# SCH_Airliner_radio.net
KiCad netlist of a schematic drawn in EasyEDA
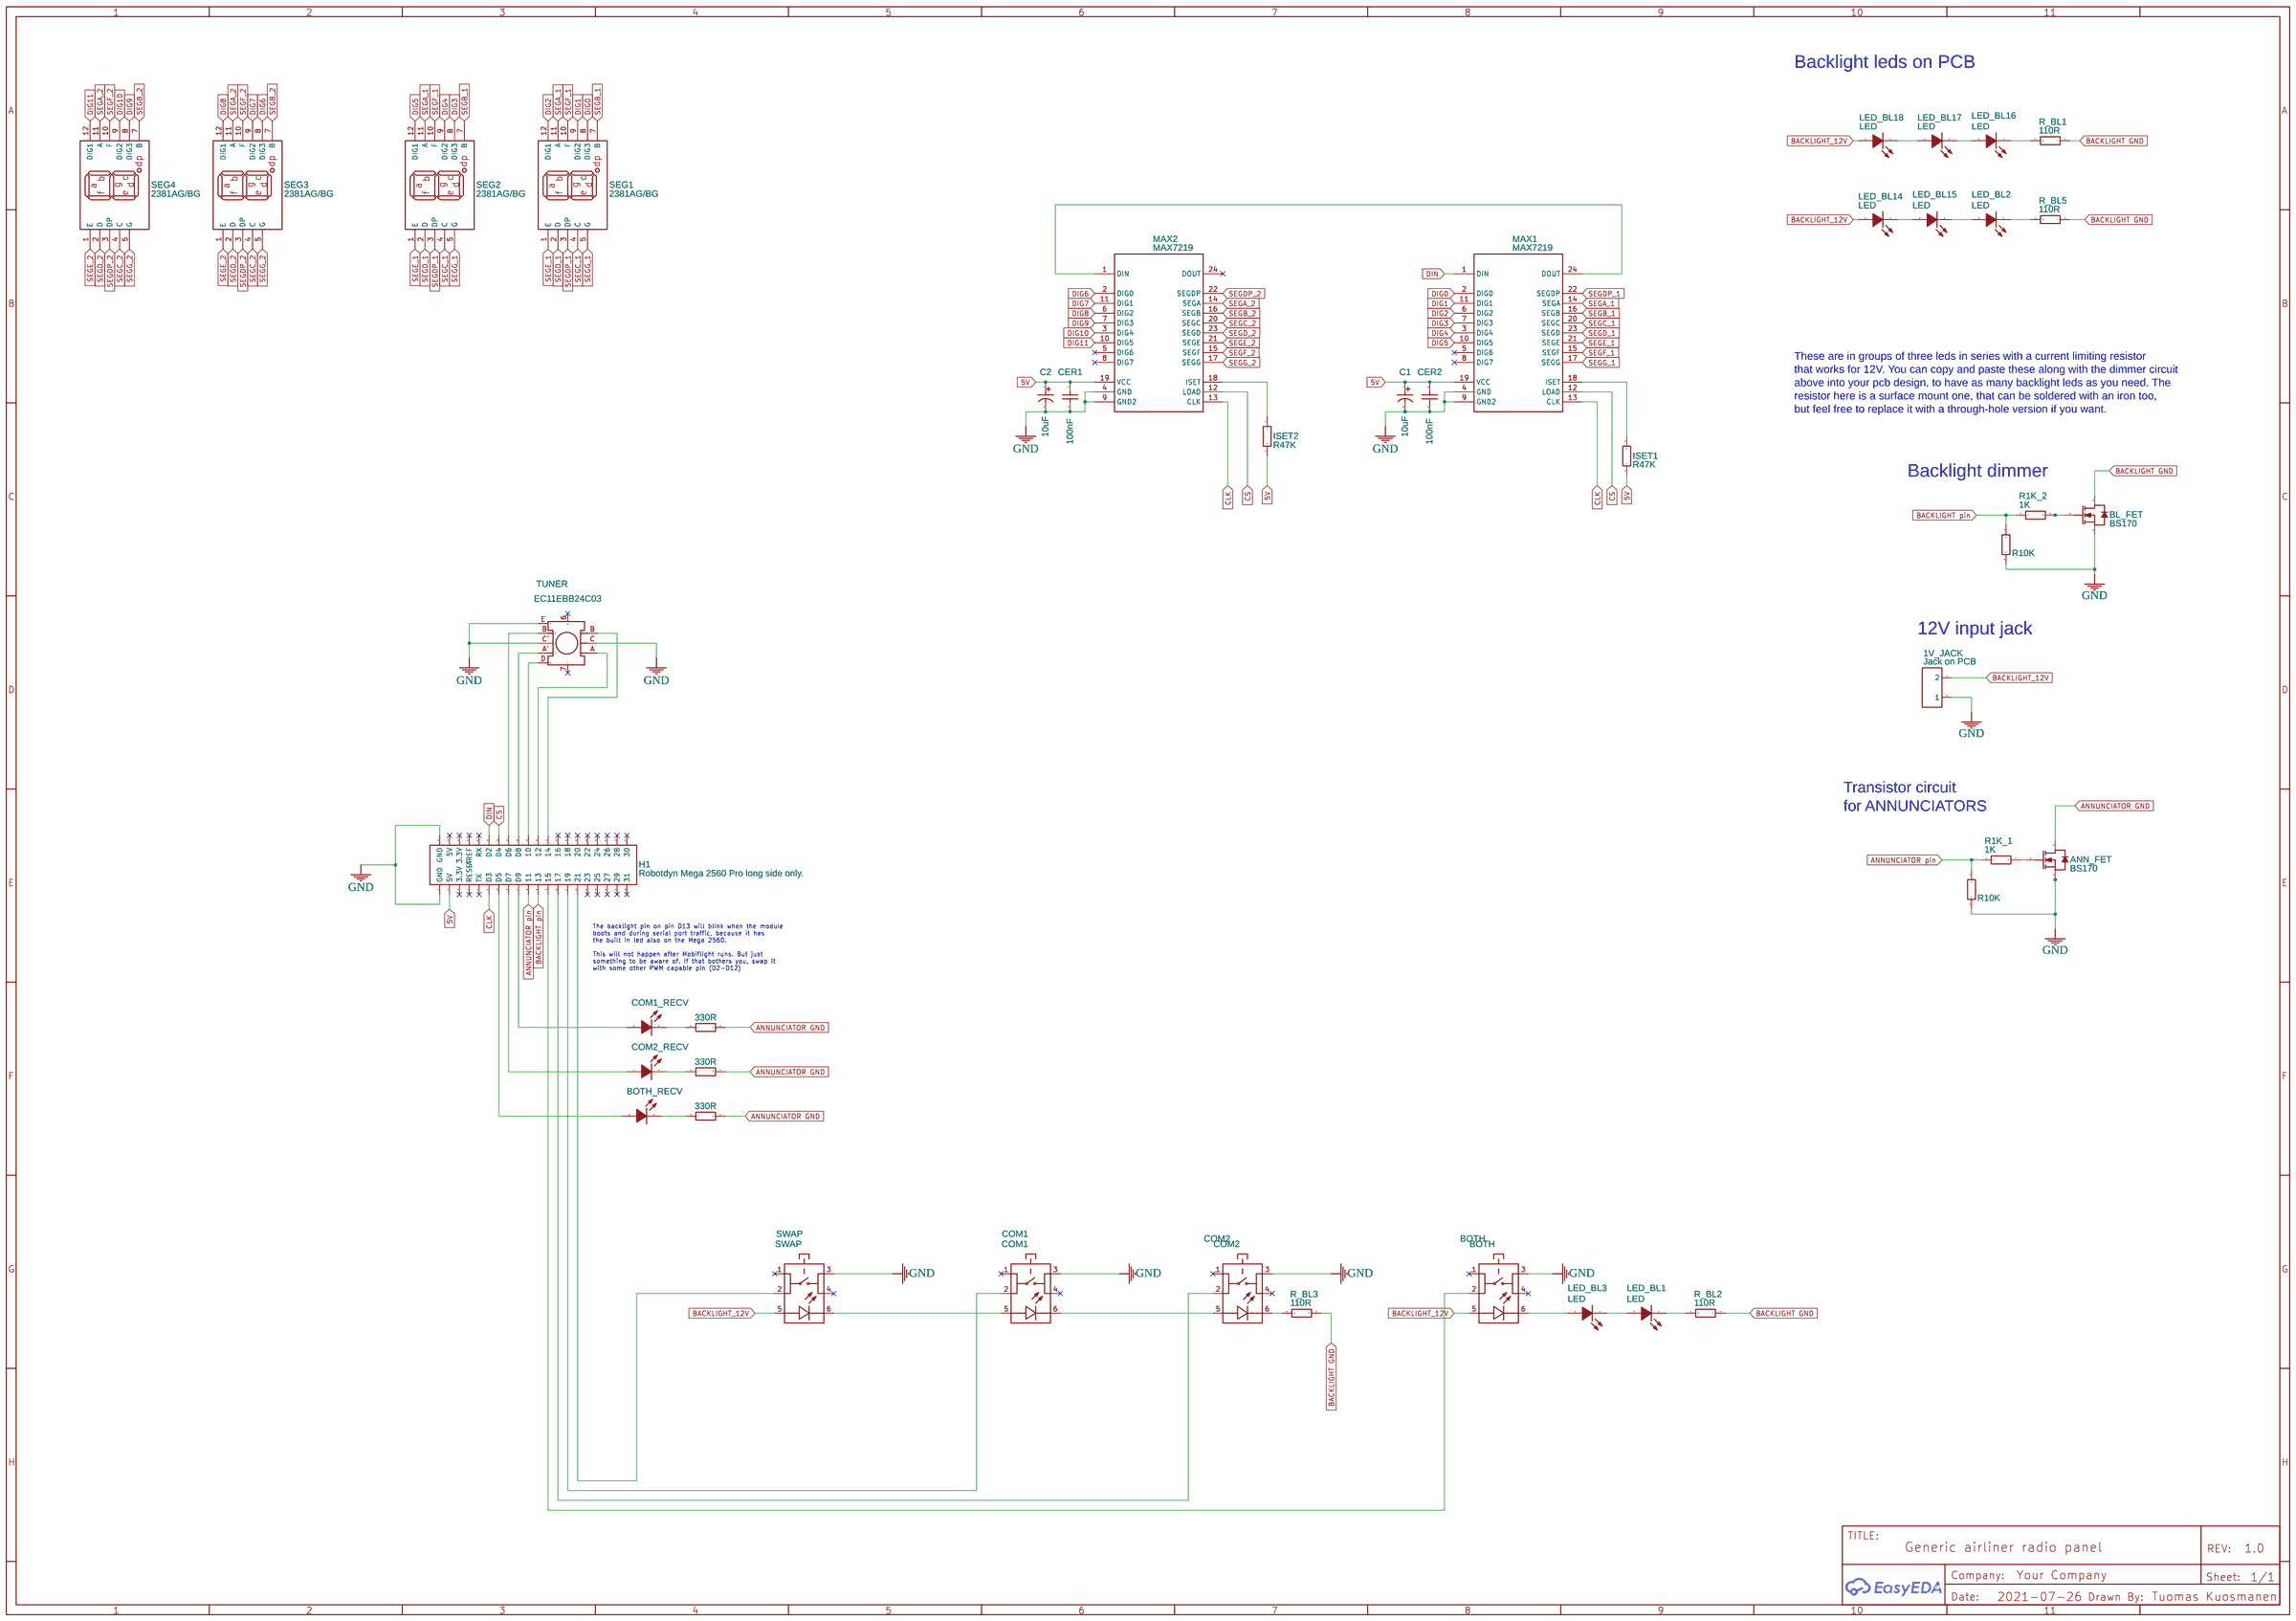
[diagram p0: schematic sheet]

(export (version "E")
  (design (tool "Eeschema 10.0.6"))
  (components
    (comp (ref "1MM_LED_THROUGH_HOLE")
      (value "COM2_RECV")
      (fields
        (field (name "BOM_Manufacturer Part") "LEDOrange orange 3AO4UD")
        (field (name "BOM_Supplier Part") "C62095")
      )
      (libsource (lib "") (part "LEDOrange orange 3AO4UD_2"))
    )
    (comp (ref "1V_JACK") (value "Jack on PCB") (libsource (lib "") (part "J-Header-Male-2.54_1x2")))
    (comp (ref "1_SURFACE_MOUNT_RESISTOR")
      (value "330R")
      (fields
        (field (name "BOM_Manufacturer Part") "1206W4F330LT5E")
        (field (name "BOM_Supplier Part") "C25337")
      )
      (libsource (lib "") (part "1206W4F330LT5E_1"))
    )
    (comp (ref "2MM_LED_THROUGH_HOLE")
      (value "BOTH_RECV")
      (fields
        (field (name "BOM_Manufacturer Part") "LEDOrange orange 3AO4UD")
        (field (name "BOM_Supplier Part") "C62095")
      )
      (libsource (lib "") (part "LEDOrange orange 3AO4UD_1"))
    )
    (comp (ref "2_SURFACE_MOUNT_RESISTOR")
      (value "330R")
      (fields
        (field (name "BOM_Manufacturer Part") "1206W4F330LT5E")
        (field (name "BOM_Supplier Part") "C25337")
      )
      (libsource (lib "") (part "1206W4F330LT5E"))
    )
    (comp (ref "3_SURFACE_MOUNT_RESISTOR")
      (value "330R")
      (fields
        (field (name "BOM_Manufacturer Part") "1206W4F330LT5E")
        (field (name "BOM_Supplier Part") "C25337")
      )
      (libsource (lib "") (part "1206W4F330LT5E_2"))
    )
    (comp (ref "5MM_LED_THROUGH_HOLE")
      (value "COM1_RECV")
      (fields
        (field (name "BOM_Manufacturer Part") "LEDOrange orange 3AO4UD")
        (field (name "BOM_Supplier Part") "C62095")
      )
      (libsource (lib "") (part "LEDOrange orange 3AO4UD"))
    )
    (comp (ref "ANN_FET")
      (value "BS170")
      (fields (field (name "BOM_Supplier Part") "C111691"))
      (libsource (lib "") (part "BS170"))
    )
    (comp (ref "BL_FET")
      (value "BS170")
      (fields (field (name "BOM_Supplier Part") "C111691"))
      (libsource (lib "") (part "BS170_1"))
    )
    (comp (ref "BOTH")
      (value "BOTH")
      (fields (field (name "BOM_Manufacturer Part") "1052612"))
      (libsource (lib "") (part "MULTIMEC 3FTH980 - Key Switch, 50 mA, 24 VDC, MEC_1"))
    )
    (comp (ref "C1")
      (value "10uF")
      (fields (field (name "BOM_Manufacturer Part") "10uf/100V") (field (name "BOM_Supplier Part") "C2029"))
      (libsource (lib "") (part "10uf/100V"))
    )
    (comp (ref "C2")
      (value "10uF")
      (fields (field (name "BOM_Manufacturer Part") "10uf/100V") (field (name "BOM_Supplier Part") "C2029"))
      (libsource (lib "") (part "10uf/100V"))
    )
    (comp (ref "CER1")
      (value "100nF")
      (fields
        (field (name "BOM_Manufacturer Part") "CS1F5.6Y5V1A104Z")
        (field (name "BOM_Supplier Part") "C9306")
      )
      (libsource (lib "") (part "CS1F5.6Y5V1A104Z"))
    )
    (comp (ref "CER2")
      (value "100nF")
      (fields
        (field (name "BOM_Manufacturer Part") "CS1F5.6Y5V1A104Z")
        (field (name "BOM_Supplier Part") "C9306")
      )
      (libsource (lib "") (part "CS1F5.6Y5V1A104Z"))
    )
    (comp (ref "COM1")
      (value "COM1")
      (fields (field (name "BOM_Manufacturer Part") "1052612"))
      (libsource (lib "") (part "MULTIMEC 3FTH980 - Key Switch, 50 mA, 24 VDC, MEC_2"))
    )
    (comp (ref "COM2")
      (value "COM2")
      (fields (field (name "BOM_Manufacturer Part") "1052612"))
      (libsource (lib "") (part "MULTIMEC 3FTH980 - Key Switch, 50 mA, 24 VDC, MEC_2"))
    )
    (comp (ref "H1")
      (value "Robotdyn Mega 2560 Pro long side only.")
      (fields
        (field (name "BOM_Manufacturer Part") "Header-Male-2.54_2x20")
        (field (name "BOM_Supplier Part") "C50980")
      )
      (libsource (lib "") (part "Header-Male-2.54_2x20"))
    )
    (comp (ref "ISET1")
      (value "R47K")
      (fields
        (field (name "BOM_Manufacturer Part") "1206W4J0331T5E")
        (field (name "BOM_Supplier Part") "C25374")
      )
      (libsource (lib "") (part "1206W4J0331T5E_3"))
    )
    (comp (ref "ISET2")
      (value "R47K")
      (fields
        (field (name "BOM_Manufacturer Part") "1206W4J0331T5E")
        (field (name "BOM_Supplier Part") "C25374")
      )
      (libsource (lib "") (part "1206W4J0331T5E_3"))
    )
    (comp (ref "LED_BL1")
      (value "LED")
      (fields
        (field (name "BOM_Manufacturer Part") "HQ17-2102UYOC")
        (field (name "BOM_Supplier Part") "C154481")
      )
      (libsource (lib "") (part "HQ17-2102UYOC"))
    )
    (comp (ref "LED_BL2")
      (value "LED")
      (fields
        (field (name "BOM_Manufacturer Part") "HQ17-2102UYOC")
        (field (name "BOM_Supplier Part") "C154481")
      )
      (libsource (lib "") (part "HQ17-2102UYOC"))
    )
    (comp (ref "LED_BL3")
      (value "LED")
      (fields
        (field (name "BOM_Manufacturer Part") "HQ17-2102UYOC")
        (field (name "BOM_Supplier Part") "C154481")
      )
      (libsource (lib "") (part "HQ17-2102UYOC"))
    )
    (comp (ref "LED_BL14")
      (value "LED")
      (fields
        (field (name "BOM_Manufacturer Part") "HQ17-2102UYOC")
        (field (name "BOM_Supplier Part") "C154481")
      )
      (libsource (lib "") (part "HQ17-2102UYOC"))
    )
    (comp (ref "LED_BL15")
      (value "LED")
      (fields
        (field (name "BOM_Manufacturer Part") "HQ17-2102UYOC")
        (field (name "BOM_Supplier Part") "C154481")
      )
      (libsource (lib "") (part "HQ17-2102UYOC"))
    )
    (comp (ref "LED_BL16")
      (value "LED")
      (fields
        (field (name "BOM_Manufacturer Part") "HQ17-2102UYOC")
        (field (name "BOM_Supplier Part") "C154481")
      )
      (libsource (lib "") (part "HQ17-2102UYOC"))
    )
    (comp (ref "LED_BL17")
      (value "LED")
      (fields
        (field (name "BOM_Manufacturer Part") "HQ17-2102UYOC")
        (field (name "BOM_Supplier Part") "C154481")
      )
      (libsource (lib "") (part "HQ17-2102UYOC"))
    )
    (comp (ref "LED_BL18")
      (value "LED")
      (fields
        (field (name "BOM_Manufacturer Part") "HQ17-2102UYOC")
        (field (name "BOM_Supplier Part") "C154481")
      )
      (libsource (lib "") (part "HQ17-2102UYOC"))
    )
    (comp (ref "MAX1") (value "MAX7219") (libsource (lib "") (part "MAX7219")))
    (comp (ref "MAX2") (value "MAX7219") (libsource (lib "") (part "MAX7219")))
    (comp (ref "R1K_1")
      (value "1K")
      (fields
        (field (name "BOM_Manufacturer Part") "1206W4J0331T5E")
        (field (name "BOM_Supplier Part") "C25374")
      )
      (libsource (lib "") (part "1206W4J0331T5E_2"))
    )
    (comp (ref "R1K_2")
      (value "1K")
      (fields
        (field (name "BOM_Manufacturer Part") "1206W4J0331T5E")
        (field (name "BOM_Supplier Part") "C25374")
      )
      (libsource (lib "") (part "1206W4J0331T5E_2"))
    )
    (comp (ref "R_ANN1")
      (value "R10K")
      (fields
        (field (name "BOM_Manufacturer Part") "1206W4J0331T5E")
        (field (name "BOM_Supplier Part") "C25374")
      )
      (libsource (lib "") (part "1206W4J0331T5E_1"))
    )
    (comp (ref "R_ANN5")
      (value "R10K")
      (fields
        (field (name "BOM_Manufacturer Part") "1206W4J0331T5E")
        (field (name "BOM_Supplier Part") "C25374")
      )
      (libsource (lib "") (part "1206W4J0331T5E_1"))
    )
    (comp (ref "R_BL1")
      (value "110R")
      (fields
        (field (name "BOM_Manufacturer Part") "1206W4J0331T5E")
        (field (name "BOM_Supplier Part") "C25374")
      )
      (libsource (lib "") (part "1206W4J0331T5E"))
    )
    (comp (ref "R_BL2")
      (value "110R")
      (fields
        (field (name "BOM_Manufacturer Part") "1206W4J0331T5E")
        (field (name "BOM_Supplier Part") "C25374")
      )
      (libsource (lib "") (part "1206W4J0331T5E"))
    )
    (comp (ref "R_BL3")
      (value "110R")
      (fields
        (field (name "BOM_Manufacturer Part") "1206W4J0331T5E")
        (field (name "BOM_Supplier Part") "C25374")
      )
      (libsource (lib "") (part "1206W4J0331T5E"))
    )
    (comp (ref "R_BL5")
      (value "110R")
      (fields
        (field (name "BOM_Manufacturer Part") "1206W4J0331T5E")
        (field (name "BOM_Supplier Part") "C25374")
      )
      (libsource (lib "") (part "1206W4J0331T5E"))
    )
    (comp (ref "SEG1") (value "2381AG/BG") (libsource (lib "") (part "2381AG/BG")))
    (comp (ref "SEG2") (value "2381AG/BG") (libsource (lib "") (part "2381AG/BG")))
    (comp (ref "SEG3") (value "2381AG/BG") (libsource (lib "") (part "2381AG/BG")))
    (comp (ref "SEG4") (value "2381AG/BG") (libsource (lib "") (part "2381AG/BG")))
    (comp (ref "SWAP")
      (value "SWAP")
      (fields (field (name "BOM_Manufacturer Part") "1052612"))
      (libsource (lib "") (part "MULTIMEC 3FTH980 - Key Switch, 50 mA, 24 VDC, MEC"))
    )
    (comp (ref "TUNER")
      (value "EC11EBB24C03")
      (fields (field (name "BOM_Supplier Part") "C470790"))
      (libsource (lib "") (part "EC11EBB24C03"))
    )
  )
  (nets
    (net (code "1") (name "5V") (class "Default")
      (node (ref "C1") (pin "1") (pinfunction "1_1") (pintype "input"))
      (node (ref "C2") (pin "1") (pinfunction "1_1") (pintype "input"))
      (node (ref "CER1") (pin "2") (pinfunction "2_2") (pintype "input"))
      (node (ref "CER2") (pin "2") (pinfunction "2_2") (pintype "input"))
      (node (ref "H1") (pin "3") (pinfunction "5V_3") (pintype "input"))
      (node (ref "ISET1") (pin "1") (pinfunction "1_1") (pintype "input"))
      (node (ref "ISET2") (pin "1") (pinfunction "1_1") (pintype "input"))
      (node (ref "MAX1") (pin "19") (pinfunction "VCC_19") (pintype "unspecified"))
      (node (ref "MAX2") (pin "19") (pinfunction "VCC_19") (pintype "unspecified"))
    )
    (net (code "2") (name "ANNUNCIATOR GND") (class "Default")
      (node (ref "1_SURFACE_MOUNT_RESISTOR") (pin "2") (pinfunction "2_2") (pintype "input"))
      (node (ref "2_SURFACE_MOUNT_RESISTOR") (pin "2") (pinfunction "2_2") (pintype "input"))
      (node (ref "3_SURFACE_MOUNT_RESISTOR") (pin "2") (pinfunction "2_2") (pintype "input"))
      (node (ref "ANN_FET") (pin "1") (pinfunction "D_1") (pintype "unspecified"))
    )
    (net (code "3") (name "ANNUNCIATOR pin") (class "Default")
      (node (ref "H1") (pin "19") (pinfunction "11_19") (pintype "input"))
      (node (ref "R1K_1") (pin "2") (pinfunction "2_2") (pintype "input"))
      (node (ref "R_ANN1") (pin "1") (pinfunction "1_1") (pintype "input"))
    )
    (net (code "4") (name "BACKLIGHT GND") (class "Default")
      (node (ref "BL_FET") (pin "1") (pinfunction "D_1") (pintype "unspecified"))
      (node (ref "R_BL1") (pin "1") (pinfunction "1_1") (pintype "input"))
      (node (ref "R_BL2") (pin "1") (pinfunction "1_1") (pintype "input"))
      (node (ref "R_BL3") (pin "1") (pinfunction "1_1") (pintype "input"))
      (node (ref "R_BL5") (pin "1") (pinfunction "1_1") (pintype "input"))
    )
    (net (code "5") (name "BACKLIGHT pin") (class "Default")
      (node (ref "H1") (pin "21") (pinfunction "13_21") (pintype "input"))
      (node (ref "R1K_2") (pin "2") (pinfunction "2_2") (pintype "input"))
      (node (ref "R_ANN5") (pin "1") (pinfunction "1_1") (pintype "input"))
    )
    (net (code "6") (name "BACKLIGHT_12V") (class "Default")
      (node (ref "1V_JACK") (pin "2") (pinfunction "2_2") (pintype "unspecified"))
      (node (ref "BOTH") (pin "5") (pinfunction "2_5") (pintype "unspecified"))
      (node (ref "LED_BL14") (pin "2") (pinfunction "A_2") (pintype "unspecified"))
      (node (ref "LED_BL18") (pin "2") (pinfunction "A_2") (pintype "unspecified"))
      (node (ref "SWAP") (pin "5") (pinfunction "2_5") (pintype "unspecified"))
    )
    (net (code "7") (name "CLK") (class "Default")
      (node (ref "H1") (pin "11") (pinfunction "D3_11") (pintype "input"))
      (node (ref "MAX1") (pin "13") (pinfunction "CLK_13") (pintype "unspecified"))
      (node (ref "MAX2") (pin "13") (pinfunction "CLK_13") (pintype "unspecified"))
    )
    (net (code "8") (name "CS") (class "Default")
      (node (ref "H1") (pin "14") (pinfunction "D4_14") (pintype "input"))
      (node (ref "MAX1") (pin "12") (pinfunction "LOAD_12") (pintype "unspecified"))
      (node (ref "MAX2") (pin "12") (pinfunction "LOAD_12") (pintype "unspecified"))
    )
    (net (code "9") (name "DIG0") (class "Default")
      (node (ref "MAX1") (pin "2") (pinfunction "DIG0_2") (pintype "unspecified"))
      (node (ref "SEG1") (pin "8") (pinfunction "DIG3_8") (pintype "input"))
    )
    (net (code "10") (name "DIG1") (class "Default")
      (node (ref "MAX1") (pin "11") (pinfunction "DIG1_11") (pintype "unspecified"))
      (node (ref "SEG1") (pin "9") (pinfunction "DIG2_9") (pintype "input"))
    )
    (net (code "11") (name "DIG2") (class "Default")
      (node (ref "MAX1") (pin "6") (pinfunction "DIG2_6") (pintype "unspecified"))
      (node (ref "SEG1") (pin "12") (pinfunction "DIG1_12") (pintype "input"))
    )
    (net (code "12") (name "DIG3") (class "Default")
      (node (ref "MAX1") (pin "7") (pinfunction "DIG3_7") (pintype "unspecified"))
      (node (ref "SEG2") (pin "8") (pinfunction "DIG3_8") (pintype "input"))
    )
    (net (code "13") (name "DIG4") (class "Default")
      (node (ref "MAX1") (pin "3") (pinfunction "DIG4_3") (pintype "unspecified"))
      (node (ref "SEG2") (pin "9") (pinfunction "DIG2_9") (pintype "input"))
    )
    (net (code "14") (name "DIG5") (class "Default")
      (node (ref "MAX1") (pin "10") (pinfunction "DIG5_10") (pintype "unspecified"))
      (node (ref "SEG2") (pin "12") (pinfunction "DIG1_12") (pintype "input"))
    )
    (net (code "15") (name "DIG6") (class "Default")
      (node (ref "MAX2") (pin "2") (pinfunction "DIG0_2") (pintype "unspecified"))
      (node (ref "SEG3") (pin "8") (pinfunction "DIG3_8") (pintype "input"))
    )
    (net (code "16") (name "DIG7") (class "Default")
      (node (ref "MAX2") (pin "11") (pinfunction "DIG1_11") (pintype "unspecified"))
      (node (ref "SEG3") (pin "9") (pinfunction "DIG2_9") (pintype "input"))
    )
    (net (code "17") (name "DIG8") (class "Default")
      (node (ref "MAX2") (pin "6") (pinfunction "DIG2_6") (pintype "unspecified"))
      (node (ref "SEG3") (pin "12") (pinfunction "DIG1_12") (pintype "input"))
    )
    (net (code "18") (name "DIG9") (class "Default")
      (node (ref "MAX2") (pin "7") (pinfunction "DIG3_7") (pintype "unspecified"))
      (node (ref "SEG4") (pin "8") (pinfunction "DIG3_8") (pintype "input"))
    )
    (net (code "19") (name "DIG10") (class "Default")
      (node (ref "MAX2") (pin "3") (pinfunction "DIG4_3") (pintype "unspecified"))
      (node (ref "SEG4") (pin "9") (pinfunction "DIG2_9") (pintype "input"))
    )
    (net (code "20") (name "DIG11") (class "Default")
      (node (ref "MAX2") (pin "10") (pinfunction "DIG5_10") (pintype "unspecified"))
      (node (ref "SEG4") (pin "12") (pinfunction "DIG1_12") (pintype "input"))
    )
    (net (code "21") (name "DIN") (class "Default")
      (node (ref "H1") (pin "12") (pinfunction "D2_12") (pintype "input"))
      (node (ref "MAX1") (pin "1") (pinfunction "DIN_1") (pintype "unspecified"))
    )
    (net (code "22") (name "GND") (class "Default")
      (node (ref "1V_JACK") (pin "1") (pinfunction "1_1") (pintype "unspecified"))
      (node (ref "ANN_FET") (pin "3") (pinfunction "S_3") (pintype "unspecified"))
      (node (ref "BL_FET") (pin "3") (pinfunction "S_3") (pintype "unspecified"))
      (node (ref "BOTH") (pin "3") (pinfunction "3_3") (pintype "unspecified"))
      (node (ref "C1") (pin "2") (pinfunction "2_2") (pintype "input"))
      (node (ref "C2") (pin "2") (pinfunction "2_2") (pintype "input"))
      (node (ref "CER1") (pin "1") (pinfunction "1_1") (pintype "input"))
      (node (ref "CER2") (pin "1") (pinfunction "1_1") (pintype "input"))
      (node (ref "COM1") (pin "3") (pinfunction "3_3") (pintype "unspecified"))
      (node (ref "COM2") (pin "3") (pinfunction "3_3") (pintype "unspecified"))
      (node (ref "H1") (pin "1") (pinfunction "GND_1") (pintype "input"))
      (node (ref "H1") (pin "2") (pinfunction "GND_2") (pintype "input"))
      (node (ref "MAX1") (pin "4") (pinfunction "GND_4") (pintype "unspecified"))
      (node (ref "MAX1") (pin "9") (pinfunction "GND2_9") (pintype "unspecified"))
      (node (ref "MAX2") (pin "4") (pinfunction "GND_4") (pintype "unspecified"))
      (node (ref "MAX2") (pin "9") (pinfunction "GND2_9") (pintype "unspecified"))
      (node (ref "R_ANN1") (pin "2") (pinfunction "2_2") (pintype "input"))
      (node (ref "R_ANN5") (pin "2") (pinfunction "2_2") (pintype "input"))
      (node (ref "SWAP") (pin "3") (pinfunction "3_3") (pintype "unspecified"))
      (node (ref "TUNER") (pin "C") (pinfunction "C_C") (pintype "unspecified"))
      (node (ref "TUNER") (pin "C'") (pinfunction "C'_C'") (pintype "unspecified"))
      (node (ref "TUNER") (pin "E") (pinfunction "E_E") (pintype "unspecified"))
    )
    (net (code "23") (name "Net-(1MM_LED_THROUGH_HOLE-A)") (class "Default")
      (node (ref "1MM_LED_THROUGH_HOLE") (pin "1") (pinfunction "A_1") (pintype "unspecified"))
      (node (ref "H1") (pin "15") (pinfunction "D7_15") (pintype "input"))
    )
    (net (code "24") (name "Net-(1MM_LED_THROUGH_HOLE-K)") (class "Default")
      (node (ref "1MM_LED_THROUGH_HOLE") (pin "2") (pinfunction "K_2") (pintype "unspecified"))
      (node (ref "1_SURFACE_MOUNT_RESISTOR") (pin "1") (pinfunction "1_1") (pintype "input"))
    )
    (net (code "25") (name "Net-(2MM_LED_THROUGH_HOLE-A)") (class "Default")
      (node (ref "2MM_LED_THROUGH_HOLE") (pin "1") (pinfunction "A_1") (pintype "unspecified"))
      (node (ref "H1") (pin "13") (pinfunction "D5_13") (pintype "input"))
    )
    (net (code "26") (name "Net-(2MM_LED_THROUGH_HOLE-K)") (class "Default")
      (node (ref "2MM_LED_THROUGH_HOLE") (pin "2") (pinfunction "K_2") (pintype "unspecified"))
      (node (ref "3_SURFACE_MOUNT_RESISTOR") (pin "1") (pinfunction "1_1") (pintype "input"))
    )
    (net (code "27") (name "Net-(5MM_LED_THROUGH_HOLE-A)") (class "Default")
      (node (ref "5MM_LED_THROUGH_HOLE") (pin "1") (pinfunction "A_1") (pintype "unspecified"))
      (node (ref "H1") (pin "17") (pinfunction "D9_17") (pintype "input"))
    )
    (net (code "28") (name "Net-(5MM_LED_THROUGH_HOLE-K)") (class "Default")
      (node (ref "2_SURFACE_MOUNT_RESISTOR") (pin "1") (pinfunction "1_1") (pintype "input"))
      (node (ref "5MM_LED_THROUGH_HOLE") (pin "2") (pinfunction "K_2") (pintype "unspecified"))
    )
    (net (code "29") (name "Net-(ANN_FET-G)") (class "Default")
      (node (ref "ANN_FET") (pin "2") (pinfunction "G_2") (pintype "unspecified"))
      (node (ref "R1K_1") (pin "1") (pinfunction "1_1") (pintype "input"))
    )
    (net (code "30") (name "Net-(BL_FET-G)") (class "Default")
      (node (ref "BL_FET") (pin "2") (pinfunction "G_2") (pintype "unspecified"))
      (node (ref "R1K_2") (pin "1") (pinfunction "1_1") (pintype "input"))
    )
    (net (code "31") (name "Net-(COM1-2-Pad5)") (class "Default")
      (node (ref "COM1") (pin "5") (pinfunction "2_5") (pintype "unspecified"))
      (node (ref "SWAP") (pin "6") (pinfunction "4_6") (pintype "unspecified"))
    )
    (net (code "32") (name "Net-(COM1-4-Pad6)") (class "Default")
      (node (ref "COM1") (pin "6") (pinfunction "4_6") (pintype "unspecified"))
      (node (ref "COM2") (pin "5") (pinfunction "2_5") (pintype "unspecified"))
    )
    (net (code "33") (name "Net-(COM2-4-Pad6)") (class "Default")
      (node (ref "COM2") (pin "6") (pinfunction "4_6") (pintype "unspecified"))
      (node (ref "R_BL3") (pin "2") (pinfunction "2_2") (pintype "input"))
    )
    (net (code "34") (name "Net-(H1-10)") (class "Default")
      (node (ref "H1") (pin "20") (pinfunction "10_20") (pintype "input"))
      (node (ref "TUNER") (pin "D") (pinfunction "D_D") (pintype "unspecified"))
    )
    (net (code "35") (name "Net-(H1-12)") (class "Default")
      (node (ref "H1") (pin "22") (pinfunction "12_22") (pintype "input"))
      (node (ref "TUNER") (pin "A") (pinfunction "A_A") (pintype "unspecified"))
    )
    (net (code "36") (name "Net-(H1-14)") (class "Default")
      (node (ref "H1") (pin "24") (pinfunction "14_24") (pintype "input"))
      (node (ref "TUNER") (pin "B") (pinfunction "B_B") (pintype "unspecified"))
    )
    (net (code "37") (name "Net-(H1-15)") (class "Default")
      (node (ref "BOTH") (pin "2") (pinfunction "2_2") (pintype "unspecified"))
      (node (ref "H1") (pin "23") (pinfunction "15_23") (pintype "input"))
    )
    (net (code "38") (name "Net-(H1-17)") (class "Default")
      (node (ref "COM2") (pin "2") (pinfunction "2_2") (pintype "unspecified"))
      (node (ref "H1") (pin "25") (pinfunction "17_25") (pintype "input"))
    )
    (net (code "39") (name "Net-(H1-19)") (class "Default")
      (node (ref "COM1") (pin "2") (pinfunction "2_2") (pintype "unspecified"))
      (node (ref "H1") (pin "27") (pinfunction "19_27") (pintype "input"))
    )
    (net (code "40") (name "Net-(H1-21)") (class "Default")
      (node (ref "H1") (pin "29") (pinfunction "21_29") (pintype "input"))
      (node (ref "SWAP") (pin "2") (pinfunction "2_2") (pintype "unspecified"))
    )
    (net (code "41") (name "Net-(H1-D6)") (class "Default")
      (node (ref "H1") (pin "16") (pinfunction "D6_16") (pintype "input"))
      (node (ref "TUNER") (pin "B'") (pinfunction "B'_B'") (pintype "unspecified"))
    )
    (net (code "42") (name "Net-(H1-D8)") (class "Default")
      (node (ref "H1") (pin "18") (pinfunction "D8_18") (pintype "input"))
      (node (ref "TUNER") (pin "A'") (pinfunction "A'_A'") (pintype "unspecified"))
    )
    (net (code "43") (name "Net-(LED_BL1-A)") (class "Default")
      (node (ref "LED_BL1") (pin "2") (pinfunction "A_2") (pintype "unspecified"))
      (node (ref "LED_BL3") (pin "1") (pinfunction "K_1") (pintype "unspecified"))
    )
    (net (code "44") (name "Net-(LED_BL1-K)") (class "Default")
      (node (ref "LED_BL1") (pin "1") (pinfunction "K_1") (pintype "unspecified"))
      (node (ref "R_BL2") (pin "2") (pinfunction "2_2") (pintype "input"))
    )
    (net (code "45") (name "Net-(LED_BL2-K)") (class "Default")
      (node (ref "LED_BL2") (pin "1") (pinfunction "K_1") (pintype "unspecified"))
      (node (ref "R_BL5") (pin "2") (pinfunction "2_2") (pintype "input"))
    )
    (net (code "46") (name "Net-(LED_BL3-A)") (class "Default")
      (node (ref "BOTH") (pin "6") (pinfunction "4_6") (pintype "unspecified"))
      (node (ref "LED_BL3") (pin "2") (pinfunction "A_2") (pintype "unspecified"))
    )
    (net (code "47") (name "Net-(LED_BL14-K)") (class "Default")
      (node (ref "LED_BL14") (pin "1") (pinfunction "K_1") (pintype "unspecified"))
      (node (ref "LED_BL15") (pin "2") (pinfunction "A_2") (pintype "unspecified"))
    )
    (net (code "48") (name "Net-(LED_BL15-K)") (class "Default")
      (node (ref "LED_BL15") (pin "1") (pinfunction "K_1") (pintype "unspecified"))
      (node (ref "LED_BL2") (pin "2") (pinfunction "A_2") (pintype "unspecified"))
    )
    (net (code "49") (name "Net-(LED_BL16-A)") (class "Default")
      (node (ref "LED_BL16") (pin "2") (pinfunction "A_2") (pintype "unspecified"))
      (node (ref "LED_BL17") (pin "1") (pinfunction "K_1") (pintype "unspecified"))
    )
    (net (code "50") (name "Net-(LED_BL16-K)") (class "Default")
      (node (ref "LED_BL16") (pin "1") (pinfunction "K_1") (pintype "unspecified"))
      (node (ref "R_BL1") (pin "2") (pinfunction "2_2") (pintype "input"))
    )
    (net (code "51") (name "Net-(LED_BL17-A)") (class "Default")
      (node (ref "LED_BL17") (pin "2") (pinfunction "A_2") (pintype "unspecified"))
      (node (ref "LED_BL18") (pin "1") (pinfunction "K_1") (pintype "unspecified"))
    )
    (net (code "52") (name "Net-(MAX1-DOUT)") (class "Default")
      (node (ref "MAX1") (pin "24") (pinfunction "DOUT_24") (pintype "unspecified"))
      (node (ref "MAX2") (pin "1") (pinfunction "DIN_1") (pintype "unspecified"))
    )
    (net (code "53") (name "Net-(MAX1-ISET)") (class "Default")
      (node (ref "ISET1") (pin "2") (pinfunction "2_2") (pintype "input"))
      (node (ref "MAX1") (pin "18") (pinfunction "ISET_18") (pintype "unspecified"))
    )
    (net (code "54") (name "Net-(MAX2-ISET)") (class "Default")
      (node (ref "ISET2") (pin "2") (pinfunction "2_2") (pintype "input"))
      (node (ref "MAX2") (pin "18") (pinfunction "ISET_18") (pintype "unspecified"))
    )
    (net (code "55") (name "SEGA_1") (class "Default")
      (node (ref "MAX1") (pin "14") (pinfunction "SEGA_14") (pintype "unspecified"))
      (node (ref "SEG1") (pin "11") (pinfunction "A_11") (pintype "input"))
      (node (ref "SEG2") (pin "11") (pinfunction "A_11") (pintype "input"))
    )
    (net (code "56") (name "SEGA_2") (class "Default")
      (node (ref "MAX2") (pin "14") (pinfunction "SEGA_14") (pintype "unspecified"))
      (node (ref "SEG3") (pin "11") (pinfunction "A_11") (pintype "input"))
      (node (ref "SEG4") (pin "11") (pinfunction "A_11") (pintype "input"))
    )
    (net (code "57") (name "SEGB_1") (class "Default")
      (node (ref "MAX1") (pin "16") (pinfunction "SEGB_16") (pintype "unspecified"))
      (node (ref "SEG1") (pin "7") (pinfunction "B_7") (pintype "input"))
      (node (ref "SEG2") (pin "7") (pinfunction "B_7") (pintype "input"))
    )
    (net (code "58") (name "SEGB_2") (class "Default")
      (node (ref "MAX2") (pin "16") (pinfunction "SEGB_16") (pintype "unspecified"))
      (node (ref "SEG3") (pin "7") (pinfunction "B_7") (pintype "input"))
      (node (ref "SEG4") (pin "7") (pinfunction "B_7") (pintype "input"))
    )
    (net (code "59") (name "SEGC_1") (class "Default")
      (node (ref "MAX1") (pin "20") (pinfunction "SEGC_20") (pintype "unspecified"))
      (node (ref "SEG1") (pin "4") (pinfunction "C_4") (pintype "input"))
      (node (ref "SEG2") (pin "4") (pinfunction "C_4") (pintype "input"))
    )
    (net (code "60") (name "SEGC_2") (class "Default")
      (node (ref "MAX2") (pin "20") (pinfunction "SEGC_20") (pintype "unspecified"))
      (node (ref "SEG3") (pin "4") (pinfunction "C_4") (pintype "input"))
      (node (ref "SEG4") (pin "4") (pinfunction "C_4") (pintype "input"))
    )
    (net (code "61") (name "SEGDP_1") (class "Default")
      (node (ref "MAX1") (pin "22") (pinfunction "SEGDP_22") (pintype "unspecified"))
      (node (ref "SEG1") (pin "3") (pinfunction "DP_3") (pintype "input"))
      (node (ref "SEG2") (pin "3") (pinfunction "DP_3") (pintype "input"))
    )
    (net (code "62") (name "SEGDP_2") (class "Default")
      (node (ref "MAX2") (pin "22") (pinfunction "SEGDP_22") (pintype "unspecified"))
      (node (ref "SEG3") (pin "3") (pinfunction "DP_3") (pintype "input"))
      (node (ref "SEG4") (pin "3") (pinfunction "DP_3") (pintype "input"))
    )
    (net (code "63") (name "SEGD_1") (class "Default")
      (node (ref "MAX1") (pin "23") (pinfunction "SEGD_23") (pintype "unspecified"))
      (node (ref "SEG1") (pin "2") (pinfunction "D_2") (pintype "input"))
      (node (ref "SEG2") (pin "2") (pinfunction "D_2") (pintype "input"))
    )
    (net (code "64") (name "SEGD_2") (class "Default")
      (node (ref "MAX2") (pin "23") (pinfunction "SEGD_23") (pintype "unspecified"))
      (node (ref "SEG3") (pin "2") (pinfunction "D_2") (pintype "input"))
      (node (ref "SEG4") (pin "2") (pinfunction "D_2") (pintype "input"))
    )
    (net (code "65") (name "SEGE_1") (class "Default")
      (node (ref "MAX1") (pin "21") (pinfunction "SEGE_21") (pintype "unspecified"))
      (node (ref "SEG1") (pin "1") (pinfunction "E_1") (pintype "input"))
      (node (ref "SEG2") (pin "1") (pinfunction "E_1") (pintype "input"))
    )
    (net (code "66") (name "SEGE_2") (class "Default")
      (node (ref "MAX2") (pin "21") (pinfunction "SEGE_21") (pintype "unspecified"))
      (node (ref "SEG3") (pin "1") (pinfunction "E_1") (pintype "input"))
      (node (ref "SEG4") (pin "1") (pinfunction "E_1") (pintype "input"))
    )
    (net (code "67") (name "SEGF_1") (class "Default")
      (node (ref "MAX1") (pin "15") (pinfunction "SEGF_15") (pintype "unspecified"))
      (node (ref "SEG1") (pin "10") (pinfunction "F_10") (pintype "input"))
      (node (ref "SEG2") (pin "10") (pinfunction "F_10") (pintype "input"))
    )
    (net (code "68") (name "SEGF_2") (class "Default")
      (node (ref "MAX2") (pin "15") (pinfunction "SEGF_15") (pintype "unspecified"))
      (node (ref "SEG3") (pin "10") (pinfunction "F_10") (pintype "input"))
      (node (ref "SEG4") (pin "10") (pinfunction "F_10") (pintype "input"))
    )
    (net (code "69") (name "SEGG_1") (class "Default")
      (node (ref "MAX1") (pin "17") (pinfunction "SEGG_17") (pintype "unspecified"))
      (node (ref "SEG1") (pin "5") (pinfunction "G_5") (pintype "input"))
      (node (ref "SEG2") (pin "5") (pinfunction "G_5") (pintype "input"))
    )
    (net (code "70") (name "SEGG_2") (class "Default")
      (node (ref "MAX2") (pin "17") (pinfunction "SEGG_17") (pintype "unspecified"))
      (node (ref "SEG3") (pin "5") (pinfunction "G_5") (pintype "input"))
      (node (ref "SEG4") (pin "5") (pinfunction "G_5") (pintype "input"))
    )
    (net (code "71") (name "unconnected-(BOTH-Pad1)") (class "Default")
      (node (ref "BOTH") (pin "1") (pinfunction "1_1") (pintype "unspecified+no_connect"))
    )
    (net (code "72") (name "unconnected-(BOTH-Pad4)") (class "Default")
      (node (ref "BOTH") (pin "4") (pinfunction "4_4") (pintype "unspecified+no_connect"))
    )
    (net (code "73") (name "unconnected-(COM1-Pad1)") (class "Default")
      (node (ref "COM1") (pin "1") (pinfunction "1_1") (pintype "unspecified+no_connect"))
    )
    (net (code "74") (name "unconnected-(COM1-Pad4)") (class "Default")
      (node (ref "COM1") (pin "4") (pinfunction "4_4") (pintype "unspecified+no_connect"))
    )
    (net (code "75") (name "unconnected-(COM2-Pad1)") (class "Default")
      (node (ref "COM2") (pin "1") (pinfunction "1_1") (pintype "unspecified+no_connect"))
    )
    (net (code "76") (name "unconnected-(COM2-Pad4)") (class "Default")
      (node (ref "COM2") (pin "4") (pinfunction "4_4") (pintype "unspecified+no_connect"))
    )
    (net (code "77") (name "unconnected-(H1-3.3V-Pad5)") (class "Default")
      (node (ref "H1") (pin "5") (pinfunction "3.3V_5") (pintype "input+no_connect"))
    )
    (net (code "78") (name "unconnected-(H1-3.3V-Pad6)") (class "Default")
      (node (ref "H1") (pin "6") (pinfunction "3.3V_6") (pintype "input+no_connect"))
    )
    (net (code "79") (name "unconnected-(H1-5V-Pad4)") (class "Default")
      (node (ref "H1") (pin "4") (pinfunction "5V_4") (pintype "input+no_connect"))
    )
    (net (code "80") (name "unconnected-(H1-16-Pad26)") (class "Default")
      (node (ref "H1") (pin "26") (pinfunction "16_26") (pintype "input+no_connect"))
    )
    (net (code "81") (name "unconnected-(H1-18-Pad28)") (class "Default")
      (node (ref "H1") (pin "28") (pinfunction "18_28") (pintype "input+no_connect"))
    )
    (net (code "82") (name "unconnected-(H1-20-Pad30)") (class "Default")
      (node (ref "H1") (pin "30") (pinfunction "20_30") (pintype "input+no_connect"))
    )
    (net (code "83") (name "unconnected-(H1-22-Pad32)") (class "Default")
      (node (ref "H1") (pin "32") (pinfunction "22_32") (pintype "input+no_connect"))
    )
    (net (code "84") (name "unconnected-(H1-23-Pad31)") (class "Default")
      (node (ref "H1") (pin "31") (pinfunction "23_31") (pintype "input+no_connect"))
    )
    (net (code "85") (name "unconnected-(H1-24-Pad34)") (class "Default")
      (node (ref "H1") (pin "34") (pinfunction "24_34") (pintype "input+no_connect"))
    )
    (net (code "86") (name "unconnected-(H1-25-Pad33)") (class "Default")
      (node (ref "H1") (pin "33") (pinfunction "25_33") (pintype "input+no_connect"))
    )
    (net (code "87") (name "unconnected-(H1-26-Pad36)") (class "Default")
      (node (ref "H1") (pin "36") (pinfunction "26_36") (pintype "input+no_connect"))
    )
    (net (code "88") (name "unconnected-(H1-27-Pad35)") (class "Default")
      (node (ref "H1") (pin "35") (pinfunction "27_35") (pintype "input+no_connect"))
    )
    (net (code "89") (name "unconnected-(H1-28-Pad38)") (class "Default")
      (node (ref "H1") (pin "38") (pinfunction "28_38") (pintype "input+no_connect"))
    )
    (net (code "90") (name "unconnected-(H1-29-Pad37)") (class "Default")
      (node (ref "H1") (pin "37") (pinfunction "29_37") (pintype "input+no_connect"))
    )
    (net (code "91") (name "unconnected-(H1-30-Pad40)") (class "Default")
      (node (ref "H1") (pin "40") (pinfunction "30_40") (pintype "input+no_connect"))
    )
    (net (code "92") (name "unconnected-(H1-31-Pad39)") (class "Default")
      (node (ref "H1") (pin "39") (pinfunction "31_39") (pintype "input+no_connect"))
    )
    (net (code "93") (name "unconnected-(H1-AREF-Pad8)") (class "Default")
      (node (ref "H1") (pin "8") (pinfunction "AREF_8") (pintype "input+no_connect"))
    )
    (net (code "94") (name "unconnected-(H1-RESET-Pad7)") (class "Default")
      (node (ref "H1") (pin "7") (pinfunction "RESET_7") (pintype "input+no_connect"))
    )
    (net (code "95") (name "unconnected-(H1-RX-Pad10)") (class "Default")
      (node (ref "H1") (pin "10") (pinfunction "RX_10") (pintype "input+no_connect"))
    )
    (net (code "96") (name "unconnected-(H1-TX-Pad9)") (class "Default")
      (node (ref "H1") (pin "9") (pinfunction "TX_9") (pintype "input+no_connect"))
    )
    (net (code "97") (name "unconnected-(MAX1-DIG6-Pad5)") (class "Default")
      (node (ref "MAX1") (pin "5") (pinfunction "DIG6_5") (pintype "unspecified+no_connect"))
    )
    (net (code "98") (name "unconnected-(MAX1-DIG7-Pad8)") (class "Default")
      (node (ref "MAX1") (pin "8") (pinfunction "DIG7_8") (pintype "unspecified+no_connect"))
    )
    (net (code "99") (name "unconnected-(MAX2-DIG6-Pad5)") (class "Default")
      (node (ref "MAX2") (pin "5") (pinfunction "DIG6_5") (pintype "unspecified+no_connect"))
    )
    (net (code "100") (name "unconnected-(MAX2-DIG7-Pad8)") (class "Default")
      (node (ref "MAX2") (pin "8") (pinfunction "DIG7_8") (pintype "unspecified+no_connect"))
    )
    (net (code "101") (name "unconnected-(MAX2-DOUT-Pad24)") (class "Default")
      (node (ref "MAX2") (pin "24") (pinfunction "DOUT_24") (pintype "unspecified+no_connect"))
    )
    (net (code "102") (name "unconnected-(SWAP-Pad1)") (class "Default")
      (node (ref "SWAP") (pin "1") (pinfunction "1_1") (pintype "unspecified+no_connect"))
    )
    (net (code "103") (name "unconnected-(SWAP-Pad4)") (class "Default")
      (node (ref "SWAP") (pin "4") (pinfunction "4_4") (pintype "unspecified+no_connect"))
    )
    (net (code "104") (name "unconnected-(TUNER-Pad6)") (class "Default")
      (node (ref "TUNER") (pin "6") (pinfunction "6_6") (pintype "unspecified+no_connect"))
    )
    (net (code "105") (name "unconnected-(TUNER-Pad7)") (class "Default")
      (node (ref "TUNER") (pin "7") (pinfunction "7_7") (pintype "unspecified+no_connect"))
    )
  )
)
